# satsha-ttl.net
KiCad netlist of a schematic drawn in EAGLE
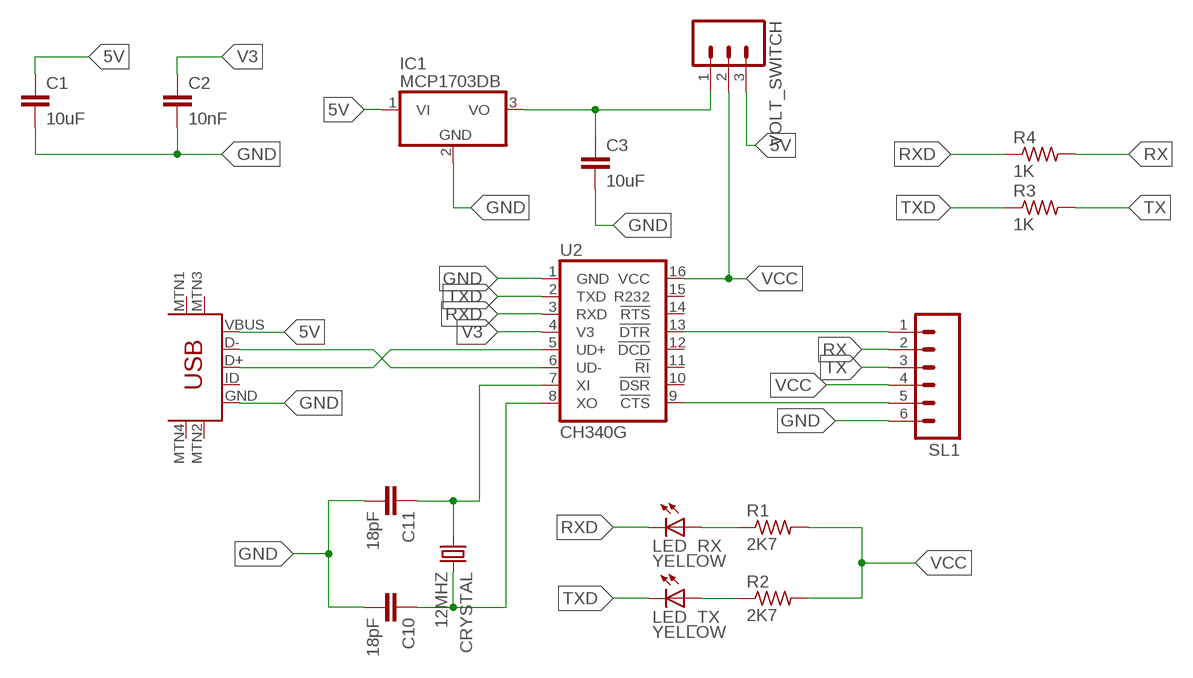
[diagram p0: schematic, sheet 1]

(export (version "E")
  (design (tool "Eeschema 10.0.6"))
  (components
    (comp (ref "C1")
      (value "10uF")
      (footprint "eagle-import:1206")
      (libsource (lib "eagle-import") (part "CAP1206"))
    )
    (comp (ref "C2")
      (value "10nF")
      (footprint "eagle-import:1206")
      (libsource (lib "eagle-import") (part "CAP1206"))
    )
    (comp (ref "C3")
      (value "10uF")
      (footprint "eagle-import:1206")
      (libsource (lib "eagle-import") (part "CAP1206"))
    )
    (comp (ref "C10")
      (value "18pF")
      (footprint "eagle-import:1206")
      (libsource (lib "eagle-import") (part "CAP1206"))
    )
    (comp (ref "C11")
      (value "18pF")
      (footprint "eagle-import:1206")
      (libsource (lib "eagle-import") (part "CAP1206"))
    )
    (comp (ref "CRYSTAL")
      (value "12MHZ")
      (footprint "eagle-import:CSM-7X-DU")
      (libsource (lib "eagle-import") (part "CSM-7X-DU"))
    )
    (comp (ref "IC1")
      (value "MCP1703DB")
      (footprint "eagle-import:SOT223")
      (libsource (lib "eagle-import") (part "MCP1703DB"))
    )
    (comp (ref "LED_RX")
      (value "YELLOW")
      (footprint "eagle-import:LED1206")
      (libsource (lib "eagle-import") (part "LED"))
    )
    (comp (ref "LED_TX")
      (value "YELLOW")
      (footprint "eagle-import:LED1206")
      (libsource (lib "eagle-import") (part "LED"))
    )
    (comp (ref "R1")
      (value "2K7")
      (footprint "eagle-import:R1206")
      (libsource (lib "eagle-import") (part "RES-US1206"))
    )
    (comp (ref "R2")
      (value "2K7")
      (footprint "eagle-import:R1206")
      (libsource (lib "eagle-import") (part "RES-US1206"))
    )
    (comp (ref "R3")
      (value "1K")
      (footprint "eagle-import:R1206")
      (libsource (lib "eagle-import") (part "RES-US1206"))
    )
    (comp (ref "R4")
      (value "1K")
      (footprint "eagle-import:R1206")
      (libsource (lib "eagle-import") (part "RES-US1206"))
    )
    (comp (ref "SL1")
      (value "M06")
      (footprint "eagle-import:06P")
      (libsource (lib "eagle-import") (part "M06"))
    )
    (comp (ref "U$7")
      (value "USB-MINIB-5PIN")
      (footprint "eagle-import:USB-MINIB")
      (libsource (lib "eagle-import") (part "USB-MINIB-5PIN"))
    )
    (comp (ref "U2")
      (value "CH340G")
      (footprint "eagle-import:SO016")
      (libsource (lib "eagle-import") (part "CH340GSMD"))
    )
    (comp (ref "VOLT_SWITCH")
      (value "M03")
      (footprint "eagle-import:03P")
      (libsource (lib "eagle-import") (part "M03"))
    )
  )
  (nets
    (net (code "1") (name "5V") (class "Default")
      (node (ref "C1") (pin "1") (pinfunction "1_1") (pintype "passive"))
      (node (ref "IC1") (pin "1") (pinfunction "VI_1") (pintype "input"))
      (node (ref "U$7") (pin "VBUS") (pinfunction "VBUS_VBUS") (pintype "bidirectional"))
      (node (ref "VOLT_SWITCH") (pin "3") (pinfunction "3_3") (pintype "passive"))
    )
    (net (code "2") (name "GND") (class "Default")
      (node (ref "C1") (pin "2") (pinfunction "2_2") (pintype "passive"))
      (node (ref "C10") (pin "2") (pinfunction "2_2") (pintype "passive"))
      (node (ref "C11") (pin "2") (pinfunction "2_2") (pintype "passive"))
      (node (ref "C2") (pin "2") (pinfunction "2_2") (pintype "passive"))
      (node (ref "C3") (pin "2") (pinfunction "2_2") (pintype "passive"))
      (node (ref "IC1") (pin "2") (pinfunction "GND_2") (pintype "passive"))
      (node (ref "SL1") (pin "6") (pinfunction "6_6") (pintype "passive"))
      (node (ref "U$7") (pin "GND") (pinfunction "GND_GND") (pintype "bidirectional"))
      (node (ref "U2") (pin "1") (pinfunction "GND_1") (pintype "bidirectional"))
    )
    (net (code "3") (name "Net-(IC1-VO)") (class "Default")
      (node (ref "C3") (pin "1") (pinfunction "1_1") (pintype "passive"))
      (node (ref "IC1") (pin "3") (pinfunction "VO_3") (pintype "passive"))
      (node (ref "VOLT_SWITCH") (pin "1") (pinfunction "1_1") (pintype "passive"))
    )
    (net (code "4") (name "Net-(LED_RX-A)") (class "Default")
      (node (ref "LED_RX") (pin "1") (pinfunction "A_1") (pintype "passive"))
      (node (ref "R1") (pin "1") (pinfunction "1_1") (pintype "passive"))
    )
    (net (code "5") (name "Net-(LED_TX-A)") (class "Default")
      (node (ref "LED_TX") (pin "1") (pinfunction "A_1") (pintype "passive"))
      (node (ref "R2") (pin "1") (pinfunction "1_1") (pintype "passive"))
    )
    (net (code "6") (name "Net-(U2-UD+)") (class "Default")
      (node (ref "U$7") (pin "D+") (pinfunction "D+_D+") (pintype "bidirectional"))
      (node (ref "U2") (pin "5") (pinfunction "UD+_5") (pintype "bidirectional"))
    )
    (net (code "7") (name "Net-(U2-UD-)") (class "Default")
      (node (ref "U$7") (pin "D-") (pinfunction "D-_D-") (pintype "bidirectional"))
      (node (ref "U2") (pin "6") (pinfunction "UD-_6") (pintype "bidirectional"))
    )
    (net (code "8") (name "Net-(U2-XI)") (class "Default")
      (node (ref "C11") (pin "1") (pinfunction "1_1") (pintype "passive"))
      (node (ref "CRYSTAL") (pin "1") (pinfunction "1_1") (pintype "passive"))
      (node (ref "U2") (pin "7") (pinfunction "XI_7") (pintype "bidirectional"))
    )
    (net (code "9") (name "Net-(U2-XO)") (class "Default")
      (node (ref "C10") (pin "1") (pinfunction "1_1") (pintype "passive"))
      (node (ref "CRYSTAL") (pin "2") (pinfunction "2_2") (pintype "passive"))
      (node (ref "U2") (pin "8") (pinfunction "XO_8") (pintype "bidirectional"))
    )
    (net (code "10") (name "Net-(U2-~{CTS})") (class "Default")
      (node (ref "SL1") (pin "5") (pinfunction "5_5") (pintype "passive"))
      (node (ref "U2") (pin "9") (pinfunction "~{CTS}_9") (pintype "bidirectional"))
    )
    (net (code "11") (name "Net-(U2-~{DTR})") (class "Default")
      (node (ref "SL1") (pin "1") (pinfunction "1_1") (pintype "passive"))
      (node (ref "U2") (pin "13") (pinfunction "~{DTR}_13") (pintype "bidirectional"))
    )
    (net (code "12") (name "RX") (class "Default")
      (node (ref "R4") (pin "2") (pinfunction "2_2") (pintype "passive"))
      (node (ref "SL1") (pin "2") (pinfunction "2_2") (pintype "passive"))
    )
    (net (code "13") (name "RXD") (class "Default")
      (node (ref "LED_RX") (pin "2") (pinfunction "C_2") (pintype "passive"))
      (node (ref "R4") (pin "1") (pinfunction "1_1") (pintype "passive"))
      (node (ref "U2") (pin "3") (pinfunction "RXD_3") (pintype "bidirectional"))
    )
    (net (code "14") (name "TX") (class "Default")
      (node (ref "R3") (pin "2") (pinfunction "2_2") (pintype "passive"))
      (node (ref "SL1") (pin "3") (pinfunction "3_3") (pintype "passive"))
    )
    (net (code "15") (name "TXD") (class "Default")
      (node (ref "LED_TX") (pin "2") (pinfunction "C_2") (pintype "passive"))
      (node (ref "R3") (pin "1") (pinfunction "1_1") (pintype "passive"))
      (node (ref "U2") (pin "2") (pinfunction "TXD_2") (pintype "bidirectional"))
    )
    (net (code "16") (name "V3") (class "Default")
      (node (ref "C2") (pin "1") (pinfunction "1_1") (pintype "passive"))
      (node (ref "U2") (pin "4") (pinfunction "V3_4") (pintype "bidirectional"))
    )
    (net (code "17") (name "VCC") (class "Default")
      (node (ref "R1") (pin "2") (pinfunction "2_2") (pintype "passive"))
      (node (ref "R2") (pin "2") (pinfunction "2_2") (pintype "passive"))
      (node (ref "SL1") (pin "4") (pinfunction "4_4") (pintype "passive"))
      (node (ref "U2") (pin "16") (pinfunction "VCC_16") (pintype "bidirectional"))
      (node (ref "VOLT_SWITCH") (pin "2") (pinfunction "2_2") (pintype "passive"))
    )
    (net (code "18") (name "unconnected-(U$7-MTN1-PadMTN3)") (class "Default")
      (node (ref "U$7") (pin "MTN3") (pinfunction "MTN1_MTN3") (pintype "bidirectional"))
    )
    (net (code "19") (name "unconnected-(U$7-MTN2-PadMTN1)") (class "Default")
      (node (ref "U$7") (pin "MTN1") (pinfunction "MTN2_MTN1") (pintype "bidirectional"))
    )
    (net (code "20") (name "unconnected-(U$7-MTN3-PadMTN2)") (class "Default")
      (node (ref "U$7") (pin "MTN2") (pinfunction "MTN3_MTN2") (pintype "bidirectional"))
    )
    (net (code "21") (name "unconnected-(U$7-PadID)") (class "Default")
      (node (ref "U$7") (pin "ID") (pinfunction "ID_ID") (pintype "bidirectional"))
    )
    (net (code "22") (name "unconnected-(U$7-PadMTN4)") (class "Default")
      (node (ref "U$7") (pin "MTN4") (pinfunction "MTN4_MTN4") (pintype "bidirectional"))
    )
    (net (code "23") (name "unconnected-(U2-R232-Pad15)") (class "Default")
      (node (ref "U2") (pin "15") (pinfunction "R232_15") (pintype "bidirectional"))
    )
    (net (code "24") (name "unconnected-(U2-~{DCD}-Pad12)") (class "Default")
      (node (ref "U2") (pin "12") (pinfunction "~{DCD}_12") (pintype "bidirectional"))
    )
    (net (code "25") (name "unconnected-(U2-~{DSR}-Pad10)") (class "Default")
      (node (ref "U2") (pin "10") (pinfunction "~{DSR}_10") (pintype "bidirectional"))
    )
    (net (code "26") (name "unconnected-(U2-~{RI}-Pad11)") (class "Default")
      (node (ref "U2") (pin "11") (pinfunction "~{RI}_11") (pintype "bidirectional"))
    )
    (net (code "27") (name "unconnected-(U2-~{RTS}-Pad14)") (class "Default")
      (node (ref "U2") (pin "14") (pinfunction "~{RTS}_14") (pintype "bidirectional"))
    )
  )
)
